# Interace_PT100.net
KiCad netlist of a schematic drawn in Altium Designer
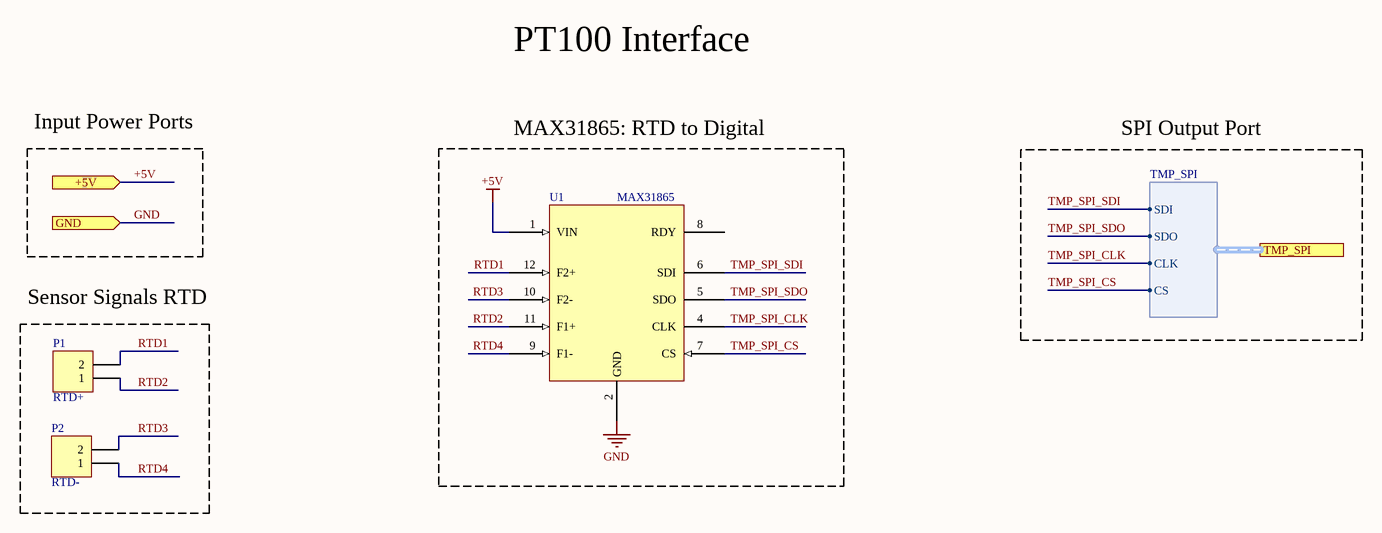
[diagram p0: Interace_PT100.SchDoc]

(export (version "E")
  (design (tool "Eeschema 10.0.6"))
  (components
    (comp (ref "P1")
      (value "RTD+")
      (footprint "HDR1X2")
      (description "Header, 2-Pin")
      (fields (field (name "PUBLISHER") "Altium Limited"))
      (libsource (lib "Miscellaneous Connectors") (part "Header 2"))
    )
    (comp (ref "P2")
      (value "RTD-")
      (footprint "HDR1X2")
      (description "Header, 2-Pin")
      (fields (field (name "PUBLISHER") "Altium Limited"))
      (libsource (lib "Miscellaneous Connectors") (part "Header 2"))
    )
    (comp (ref "U1") (value "MAX31865") (libsource (lib "SiProFaSi") (part "Adafruit MAX31865")))
  )
  (nets
    (net (code "2") (name "+5V") (class "Default")
      (node (ref "U1") (pin "1") (pinfunction "VIN_1") (pintype "input"))
    )
    (net (code "3") (name "/RTD1") (class "Default")
      (node (ref "P1") (pin "2") (pinfunction "2_2") (pintype "passive"))
      (node (ref "U1") (pin "12") (pinfunction "F2+_12") (pintype "input"))
    )
    (net (code "4") (name "/RTD2") (class "Default")
      (node (ref "P1") (pin "1") (pinfunction "1_1") (pintype "passive"))
      (node (ref "U1") (pin "11") (pinfunction "F1+_11") (pintype "input"))
    )
    (net (code "5") (name "/RTD3") (class "Default")
      (node (ref "P2") (pin "2") (pinfunction "2_2") (pintype "passive"))
      (node (ref "U1") (pin "10") (pinfunction "F2-_10") (pintype "input"))
    )
    (net (code "6") (name "/RTD4") (class "Default")
      (node (ref "P2") (pin "1") (pinfunction "1_1") (pintype "passive"))
      (node (ref "U1") (pin "9") (pinfunction "F1-_9") (pintype "input"))
    )
    (net (code "7") (name "/TMP_SPI_CLK") (class "Default")
      (node (ref "U1") (pin "4") (pinfunction "CLK_4") (pintype "passive"))
    )
    (net (code "8") (name "/TMP_SPI_CS") (class "Default")
      (node (ref "U1") (pin "7") (pinfunction "CS_7") (pintype "input"))
    )
    (net (code "9") (name "/TMP_SPI_SDI") (class "Default")
      (node (ref "U1") (pin "6") (pinfunction "SDI_6") (pintype "passive"))
    )
    (net (code "10") (name "/TMP_SPI_SDO") (class "Default")
      (node (ref "U1") (pin "5") (pinfunction "SDO_5") (pintype "passive"))
    )
    (net (code "12") (name "GND") (class "Default")
      (node (ref "U1") (pin "2") (pinfunction "GND_2") (pintype "passive"))
    )
    (net (code "13") (name "unconnected-(U1-RDY-Pad8)") (class "Default")
      (node (ref "U1") (pin "8") (pinfunction "RDY_8") (pintype "passive"))
    )
  )
)
